# 10_-MAIN_POWER.net
KiCad netlist of a schematic drawn in Altium Designer
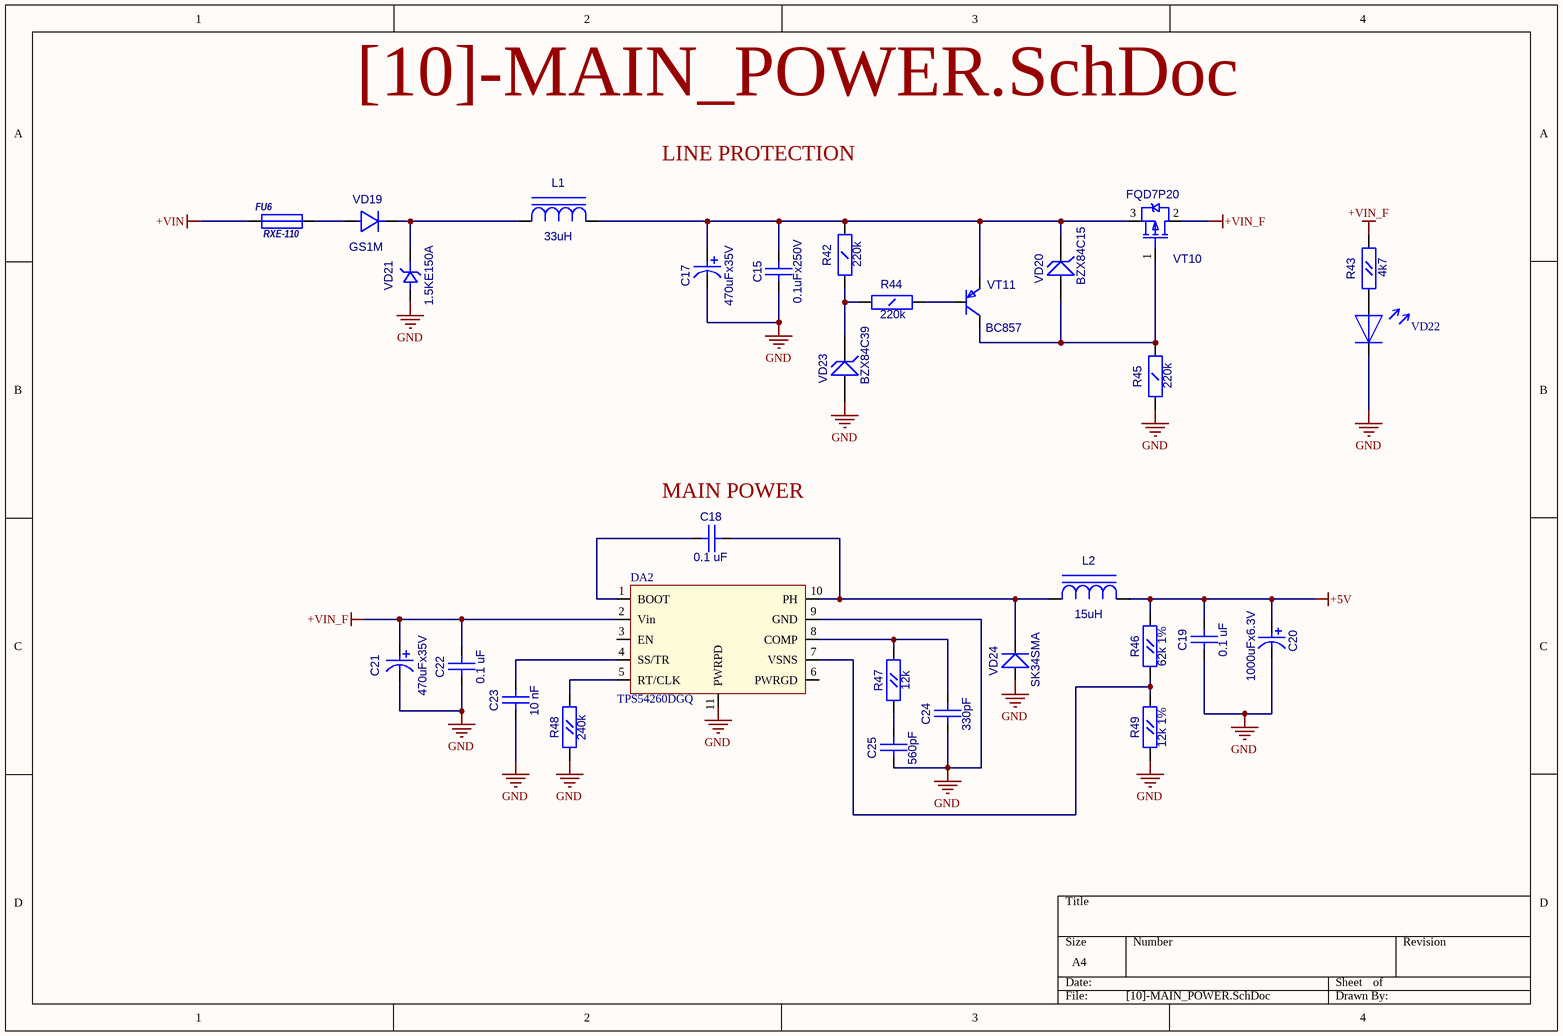
[diagram p0: [10]-MAIN_POWER.SchDoc]

(export (version "E")
  (design (tool "Eeschema 10.0.6"))
  (components
    (comp (ref "C15")
      (value "0.1uFx250V")
      (footprint "CC1206")
      (description "CC1206")
      (libsource (lib "gprs_modem_2") (part "CC1206"))
    )
    (comp (ref "C17")
      (value "470uFx35V")
      (footprint "CC16X10_CAP0.5(1)(Primary)")
      (description "CAP0.5(1)")
      (libsource (lib "gprs_modem_2") (part "CAP0.5(1)"))
    )
    (comp (ref "C18")
      (value "0.1 uF")
      (footprint "CC0603")
      (description "CC0603")
      (libsource (lib "gprs_modem_2") (part "CC0603"))
    )
    (comp (ref "C19")
      (value "0.1 uF")
      (footprint "CC0603")
      (description "CC0603")
      (libsource (lib "gprs_modem_2") (part "CC0603"))
    )
    (comp (ref "C20")
      (value "1000uFx6.3V")
      (footprint "CC8X3.5")
      (description "CAP0.35")
      (libsource (lib "gprs_modem_2") (part "CAP0.35"))
    )
    (comp (ref "C21")
      (value "470uFx35V")
      (footprint "CC16X10_CAP0.5(1)(Primary)")
      (description "CAP0.5(1)")
      (libsource (lib "gprs_modem_2") (part "CAP0.5(1)"))
    )
    (comp (ref "C22")
      (value "0.1 uF")
      (footprint "CC0603")
      (description "CC0603")
      (libsource (lib "gprs_modem_2") (part "CC0603"))
    )
    (comp (ref "C23")
      (value "10 nF")
      (footprint "CC0603")
      (description "CC0603")
      (libsource (lib "gprs_modem_2") (part "CC0603"))
    )
    (comp (ref "C24")
      (value "330pF")
      (footprint "CC0603")
      (description "CC0603")
      (libsource (lib "gprs_modem_2") (part "CC0603"))
    )
    (comp (ref "C25")
      (value "560pF")
      (footprint "CC0603")
      (description "CC0603")
      (libsource (lib "gprs_modem_2") (part "CC0603"))
    )
    (comp (ref "DA2")
      (value "TPS54260DGQ")
      (footprint "S-PDSO-G10")
      (libsource (lib "gprs_modem_2") (part "TPS54260DGQ"))
    )
    (comp (ref "FU6") (value "RXE-110") (footprint "RXE-110") (libsource (lib "fizik_lib") (part "RXE-110")))
    (comp (ref "L1")
      (value "33uH")
      (footprint "SDR0805")
      (description "SDR0805")
      (libsource (lib "fizik_lib") (part "SDR0805"))
    )
    (comp (ref "L2")
      (value "15uH")
      (footprint "SDR0805")
      (description "SDR0805")
      (libsource (lib "gprs_modem_2") (part "SDR0805"))
    )
    (comp (ref "R42")
      (value "220k")
      (footprint "RC1206")
      (description "RC1206")
      (libsource (lib "fizik_lib") (part "RC1206"))
    )
    (comp (ref "R43")
      (value "4k7")
      (footprint "RC0603")
      (description "RC0603")
      (libsource (lib "fizik_lib") (part "RC0603"))
    )
    (comp (ref "R44")
      (value "220k")
      (footprint "RC1206")
      (description "RC1206")
      (libsource (lib "fizik_lib") (part "RC1206"))
    )
    (comp (ref "R45")
      (value "220k")
      (footprint "RC1206")
      (description "RC1206")
      (libsource (lib "fizik_lib") (part "RC1206"))
    )
    (comp (ref "R46")
      (value "62k 1%")
      (footprint "RC0603")
      (description "RC0603")
      (libsource (lib "gprs_modem_2") (part "RC0603"))
    )
    (comp (ref "R47")
      (value "12k")
      (footprint "RC0603")
      (description "RC0603")
      (libsource (lib "gprs_modem_2") (part "RC0603"))
    )
    (comp (ref "R48")
      (value "240k")
      (footprint "RC0603")
      (description "RC0603")
      (libsource (lib "gprs_modem_2") (part "RC0603"))
    )
    (comp (ref "R49")
      (value "12k 1%")
      (footprint "RC0603")
      (description "RC0603")
      (libsource (lib "gprs_modem_2") (part "RC0603"))
    )
    (comp (ref "VD19") (value "GS1M") (footprint "SMA") (libsource (lib "fizik_lib") (part "GS1M")))
    (comp (ref "VD20")
      (value "BZX84C15")
      (footprint "SOT-23(123)")
      (description "Zener Voltage Regulator Diode")
      (libsource (lib "fizik_lib") (part "BZX84"))
    )
    (comp (ref "VD21")
      (value "1.5KE150A")
      (footprint "DO-201")
      (description "1.5KE")
      (libsource (lib "gprs_modem") (part "1.5KE"))
    )
    (comp (ref "VD22")
      (value "LED_0805")
      (footprint "LED0805")
      (libsource (lib "fizik_lib") (part "LED_0805"))
    )
    (comp (ref "VD23")
      (value "BZX84C39")
      (footprint "SOT-23(123)")
      (description "Zener Voltage Regulator Diode")
      (libsource (lib "fizik_lib") (part "BZX84"))
    )
    (comp (ref "VD24")
      (value "SK34SMA")
      (footprint "SMA")
      (description "Schottky Rectifier")
      (libsource (lib "gprs_modem") (part "SK34SMA"))
    )
    (comp (ref "VT10")
      (value "FQD7P20")
      (footprint "D-PAK(TO-252AA)")
      (description "HEXFET Power MOSFET")
      (libsource (lib "gprs_modem_2") (part "IRFR9220"))
    )
    (comp (ref "VT11")
      (value "BC857")
      (footprint "SOT-23(123)")
      (description "PNP 100ma transistor")
      (libsource (lib "gprs_modem_2") (part "BC857B"))
    )
  )
  (nets
    (net (code "1") (name "+5V") (class "Default")
      (node (ref "C19") (pin "1") (pinfunction "A_1") (pintype "passive"))
      (node (ref "C20") (pin "1") (pintype "passive"))
      (node (ref "L2") (pin "2") (pinfunction "A_2") (pintype "passive"))
      (node (ref "R46") (pin "2") (pinfunction "B_2") (pintype "passive"))
    )
    (net (code "2") (name "+VIN") (class "Default") (node (ref "FU6") (pin "1") (pintype "passive")))
    (net (code "3") (name "+VIN_F") (class "Default")
      (node (ref "C21") (pin "2") (pintype "passive"))
      (node (ref "C22") (pin "1") (pinfunction "A_1") (pintype "passive"))
      (node (ref "DA2") (pin "2") (pinfunction "Vin_2") (pintype "passive"))
      (node (ref "R43") (pin "2") (pinfunction "B_2") (pintype "passive"))
      (node (ref "VT10") (pin "2") (pinfunction "D_2") (pintype "passive"))
    )
    (net (code "4") (name "GND") (class "Default")
      (node (ref "C15") (pin "1") (pinfunction "A_1") (pintype "passive"))
      (node (ref "C17") (pin "1") (pintype "passive"))
      (node (ref "C19") (pin "2") (pinfunction "B_2") (pintype "passive"))
      (node (ref "C20") (pin "2") (pintype "passive"))
      (node (ref "C21") (pin "1") (pintype "passive"))
      (node (ref "C22") (pin "2") (pinfunction "B_2") (pintype "passive"))
      (node (ref "C23") (pin "2") (pinfunction "B_2") (pintype "passive"))
      (node (ref "C24") (pin "2") (pinfunction "B_2") (pintype "passive"))
      (node (ref "C25") (pin "2") (pinfunction "B_2") (pintype "passive"))
      (node (ref "DA2") (pin "11") (pinfunction "PWRPD_11") (pintype "passive"))
      (node (ref "DA2") (pin "9") (pinfunction "GND_9") (pintype "passive"))
      (node (ref "R45") (pin "1") (pinfunction "A_1") (pintype "passive"))
      (node (ref "R48") (pin "1") (pinfunction "A_1") (pintype "passive"))
      (node (ref "R49") (pin "1") (pinfunction "A_1") (pintype "passive"))
      (node (ref "VD21") (pin "1") (pinfunction "A_1") (pintype "passive"))
      (node (ref "VD22") (pin "2") (pintype "passive"))
      (node (ref "VD23") (pin "1") (pinfunction "A_1") (pintype "passive"))
      (node (ref "VD24") (pin "1") (pinfunction "A_1") (pintype "passive"))
    )
    (net (code "5") (name "Net-(C15-B)") (class "Default")
      (node (ref "C15") (pin "2") (pinfunction "B_2") (pintype "passive"))
      (node (ref "C17") (pin "2") (pintype "passive"))
      (node (ref "L1") (pin "2") (pinfunction "A_2") (pintype "passive"))
      (node (ref "R42") (pin "2") (pinfunction "B_2") (pintype "passive"))
      (node (ref "VD20") (pin "3") (pinfunction "K_3") (pintype "passive"))
      (node (ref "VT10") (pin "3") (pinfunction "S_3") (pintype "passive"))
      (node (ref "VT11") (pin "2") (pinfunction "E_2") (pintype "passive"))
    )
    (net (code "6") (name "Net-(C18-A)") (class "Default")
      (node (ref "C18") (pin "1") (pinfunction "A_1") (pintype "passive"))
      (node (ref "DA2") (pin "10") (pinfunction "PH_10") (pintype "passive"))
      (node (ref "L2") (pin "1") (pinfunction "C_1") (pintype "passive"))
      (node (ref "VD24") (pin "2") (pinfunction "K_2") (pintype "passive"))
    )
    (net (code "7") (name "Net-(C18-B)") (class "Default")
      (node (ref "C18") (pin "2") (pinfunction "B_2") (pintype "passive"))
      (node (ref "DA2") (pin "1") (pinfunction "BOOT_1") (pintype "passive"))
    )
    (net (code "8") (name "Net-(C23-A)") (class "Default")
      (node (ref "C23") (pin "1") (pinfunction "A_1") (pintype "passive"))
      (node (ref "DA2") (pin "4") (pinfunction "SS/TR_4") (pintype "passive"))
    )
    (net (code "9") (name "Net-(C24-A)") (class "Default")
      (node (ref "C24") (pin "1") (pinfunction "A_1") (pintype "passive"))
      (node (ref "DA2") (pin "8") (pinfunction "COMP_8") (pintype "passive"))
      (node (ref "R47") (pin "2") (pinfunction "B_2") (pintype "passive"))
    )
    (net (code "10") (name "Net-(C25-A)") (class "Default")
      (node (ref "C25") (pin "1") (pinfunction "A_1") (pintype "passive"))
      (node (ref "R47") (pin "1") (pinfunction "A_1") (pintype "passive"))
    )
    (net (code "11") (name "Net-(DA2-RT{slash}CLK)") (class "Default")
      (node (ref "DA2") (pin "5") (pinfunction "RT/CLK_5") (pintype "passive"))
      (node (ref "R48") (pin "2") (pinfunction "B_2") (pintype "passive"))
    )
    (net (code "12") (name "Net-(DA2-VSNS)") (class "Default")
      (node (ref "DA2") (pin "7") (pinfunction "VSNS_7") (pintype "passive"))
      (node (ref "R46") (pin "1") (pinfunction "A_1") (pintype "passive"))
      (node (ref "R49") (pin "2") (pinfunction "B_2") (pintype "passive"))
    )
    (net (code "13") (name "Net-(L1-C)") (class "Default")
      (node (ref "L1") (pin "1") (pinfunction "C_1") (pintype "passive"))
      (node (ref "VD19") (pin "2") (pinfunction "K_2") (pintype "passive"))
      (node (ref "VD21") (pin "2") (pinfunction "K_2") (pintype "passive"))
    )
    (net (code "14") (name "Net-(R42-A)") (class "Default")
      (node (ref "R42") (pin "1") (pinfunction "A_1") (pintype "passive"))
      (node (ref "R44") (pin "1") (pinfunction "A_1") (pintype "passive"))
      (node (ref "VD23") (pin "3") (pinfunction "K_3") (pintype "passive"))
    )
    (net (code "15") (name "Net-(R43-A)") (class "Default")
      (node (ref "R43") (pin "1") (pinfunction "A_1") (pintype "passive"))
      (node (ref "VD22") (pin "1") (pintype "passive"))
    )
    (net (code "16") (name "Net-(R44-B)") (class "Default")
      (node (ref "R44") (pin "2") (pinfunction "B_2") (pintype "passive"))
      (node (ref "VT11") (pin "1") (pinfunction "B_1") (pintype "passive"))
    )
    (net (code "17") (name "Net-(R45-B)") (class "Default")
      (node (ref "R45") (pin "2") (pinfunction "B_2") (pintype "passive"))
      (node (ref "VD20") (pin "1") (pinfunction "A_1") (pintype "passive"))
      (node (ref "VT10") (pin "1") (pinfunction "G_1") (pintype "passive"))
      (node (ref "VT11") (pin "3") (pinfunction "C_3") (pintype "passive"))
    )
    (net (code "18") (name "Net-(VD19-A)") (class "Default")
      (node (ref "FU6") (pin "2") (pintype "passive"))
      (node (ref "VD19") (pin "1") (pinfunction "A_1") (pintype "passive"))
    )
    (net (code "19") (name "unconnected-(DA2-EN-Pad3)") (class "Default")
      (node (ref "DA2") (pin "3") (pinfunction "EN_3") (pintype "passive"))
    )
    (net (code "20") (name "unconnected-(DA2-PWRGD-Pad6)") (class "Default")
      (node (ref "DA2") (pin "6") (pinfunction "PWRGD_6") (pintype "passive"))
    )
  )
)
